# LED.net
KiCad netlist of a schematic drawn in EAGLE
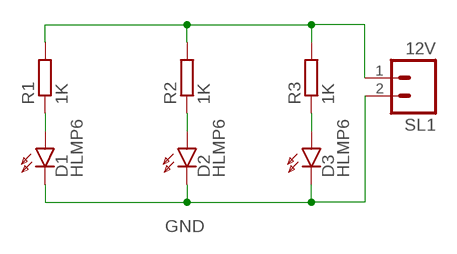
[diagram p0: schematic, sheet 1]

(export (version "E")
  (design (tool "Eeschema 10.0.6"))
  (components
    (comp (ref "D1")
      (value "HLMP6")
      (footprint "eagle-import:HLMP6")
      (fields (field (name "MF") "AGILENT TECHNOLOGIES") (field (name "MPN") "HLMP-6500"))
      (libsource (lib "eagle-import") (part "HLMP6"))
    )
    (comp (ref "D2")
      (value "HLMP6")
      (footprint "eagle-import:HLMP6")
      (fields (field (name "MF") "AGILENT TECHNOLOGIES") (field (name "MPN") "HLMP-6500"))
      (libsource (lib "eagle-import") (part "HLMP6"))
    )
    (comp (ref "D3")
      (value "HLMP6")
      (footprint "eagle-import:HLMP6")
      (fields (field (name "MF") "AGILENT TECHNOLOGIES") (field (name "MPN") "HLMP-6500"))
      (libsource (lib "eagle-import") (part "HLMP6"))
    )
    (comp (ref "R1")
      (value "1K")
      (footprint "eagle-import:0204_7")
      (libsource (lib "eagle-import") (part "R-EU_0204/7"))
    )
    (comp (ref "R2")
      (value "1K")
      (footprint "eagle-import:0204_7")
      (libsource (lib "eagle-import") (part "R-EU_0204/7"))
    )
    (comp (ref "R3")
      (value "1K")
      (footprint "eagle-import:0204_7")
      (libsource (lib "eagle-import") (part "R-EU_0204/7"))
    )
    (comp (ref "SL1")
      (value "12V")
      (footprint "eagle-import:02P")
      (libsource (lib "eagle-import") (part "M02"))
    )
  )
  (nets
    (net (code "1") (name "/GND") (class "Default")
      (node (ref "D1") (pin "K") (pinfunction "K_K") (pintype "passive"))
      (node (ref "D2") (pin "K") (pinfunction "K_K") (pintype "passive"))
      (node (ref "D3") (pin "K") (pinfunction "K_K") (pintype "passive"))
      (node (ref "SL1") (pin "2") (pinfunction "2_2") (pintype "passive"))
    )
    (net (code "2") (name "Net-(D1-PadA)") (class "Default")
      (node (ref "D1") (pin "A") (pinfunction "A_A") (pintype "passive"))
      (node (ref "R1") (pin "1") (pinfunction "1_1") (pintype "passive"))
    )
    (net (code "3") (name "Net-(D2-PadA)") (class "Default")
      (node (ref "D2") (pin "A") (pinfunction "A_A") (pintype "passive"))
      (node (ref "R2") (pin "1") (pinfunction "1_1") (pintype "passive"))
    )
    (net (code "4") (name "Net-(D3-PadA)") (class "Default")
      (node (ref "D3") (pin "A") (pinfunction "A_A") (pintype "passive"))
      (node (ref "R3") (pin "1") (pinfunction "1_1") (pintype "passive"))
    )
    (net (code "5") (name "Net-(R1-Pad2)") (class "Default")
      (node (ref "R1") (pin "2") (pinfunction "2_2") (pintype "passive"))
      (node (ref "R2") (pin "2") (pinfunction "2_2") (pintype "passive"))
      (node (ref "R3") (pin "2") (pinfunction "2_2") (pintype "passive"))
      (node (ref "SL1") (pin "1") (pinfunction "1_1") (pintype "passive"))
    )
  )
)
